# PJ30072S6_3V3_BOOST.net
KiCad netlist of a schematic drawn in Altium Designer
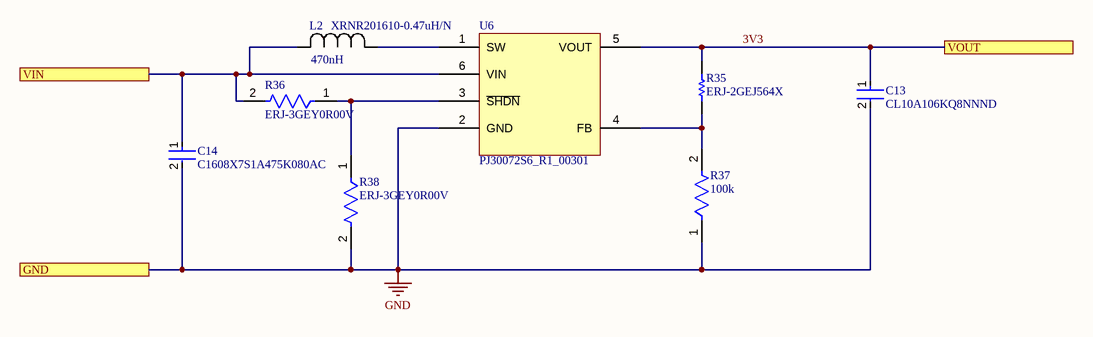
[diagram p0: PJ30072S6_3V3_BOOST.SchDoc]

(export (version "E")
  (design (tool "Eeschema 10.0.6"))
  (components
    (comp (ref "C13")
      (value "CL10A106KQ8NNND")
      (footprint "FP-CL10-IPC_C")
      (description "Cap Ceramic 10uF 6.3V X5R ±10% Pad SMD 0603 +85°C T/R")
      (fields (field (name "TOLERANCE") "10%"))
      (libsource (lib "Altium Content Vault") (part "b4654b650e69147ec39a6b967a45e02"))
    )
    (comp (ref "C14")
      (value "C1608X7S1A475K080AC")
      (footprint "FP-C1608-080-IPC_B")
      (description "CAP CER 4.7UF 10V X7S 0603")
      (fields (field (name "TOLERANCE") "10%"))
      (libsource (lib "Altium Content Vault") (part "b4654b650e69147ec39a6b967a45e02"))
    )
    (comp (ref "L2")
      (value "XRNR201610-0.47uH/N")
      (footprint "XRNR201610-0.47uH/N")
      (description "2.35A 2.3A 470nH 59mΩ Magnetic Shielded Inductor ±30% SMD-2P,2x1.6mm Power Inductors ROHS")
      (fields
        (field (name "MANUFACTURER") "Inpaq")
        (field (name "MANUFACTURER PART NUMBER") "WIP252012S-1R5MLDG")
        (field (name "INDUCTANCE") "470nH")
      )
      (libsource (lib "WIP252012S-R47MLDG") (part "XRNR201610-0.47uH/N"))
    )
    (comp (ref "R35")
      (value "ERJ-2GEJ564X")
      (footprint "RESC1005X40X25NL05T05")
      (fields (field (name "MANUFACTURER") "Panasonic"))
      (libsource (lib "Altium Content Vault") (part "RES"))
    )
    (comp (ref "R36")
      (value "ERJ-3GEY0R00V")
      (footprint "FP-ERJ-3GEY0R00V-MFG")
      (description "0 Ohms Jumper 0.1W, 1/10W Chip Resistor 0603 (1608 Metric) Automotive AEC-Q200 Thick Film")
      (fields (field (name "TOLERANCE") "5%"))
      (libsource (lib "Altium Content Vault") (part "1029c3af85768c4190bb7ad29bc67b5"))
    )
    (comp (ref "R37")
      (value "CRCW0402100KFKED")
      (footprint "FP-CRCW0402-e3-IPC_B")
      (description "RES Thick Film, 100kΩ, 1%, 0.063W, 100ppm/°C, 0402")
      (fields (field (name "RESISTANCE") "100k") (field (name "TOLERANCE") "1%"))
      (libsource (lib "Altium Content Vault") (part "1029c3af85768c4190bb7ad29bc67b5"))
    )
    (comp (ref "R38")
      (value "ERJ-3GEY0R00V")
      (footprint "FP-ERJ-3GEY0R00V-MFG")
      (description "0 Ohms Jumper 0.1W, 1/10W Chip Resistor 0603 (1608 Metric) Automotive AEC-Q200 Thick Film")
      (fields (field (name "TOLERANCE") "5%"))
      (libsource (lib "Altium Content Vault") (part "1029c3af85768c4190bb7ad29bc67b5"))
    )
    (comp (ref "U6")
      (value "PJ30072S6_R1_00301")
      (footprint "SOT95P280X15-6N")
      (description "IC REG BOOST ADJ SOT23-6")
      (libsource (lib "PJ30072S6_R1_00301") (part "PJ30072S6_R1_00301"))
    )
  )
  (nets
    (net (code "1") (name "/3V3") (class "Default")
      (node (ref "C13") (pin "1") (pinfunction "1_1") (pintype "passive"))
      (node (ref "R35") (pin "2") (pinfunction "2_2") (pintype "passive"))
      (node (ref "U6") (pin "5") (pinfunction "VOUT_5") (pintype "passive"))
    )
    (net (code "2") (name "/VIN") (class "Default")
      (node (ref "C14") (pin "1") (pinfunction "1_1") (pintype "passive"))
      (node (ref "L2") (pin "2") (pinfunction "2_2") (pintype "passive"))
      (node (ref "R36") (pin "2") (pinfunction "2_2") (pintype "passive"))
      (node (ref "U6") (pin "6") (pinfunction "VIN_6") (pintype "passive"))
    )
    (net (code "3") (name "GND") (class "Default")
      (node (ref "C13") (pin "2") (pinfunction "2_2") (pintype "passive"))
      (node (ref "C14") (pin "2") (pinfunction "2_2") (pintype "passive"))
      (node (ref "R37") (pin "1") (pinfunction "1_1") (pintype "passive"))
      (node (ref "R38") (pin "2") (pinfunction "2_2") (pintype "passive"))
      (node (ref "U6") (pin "2") (pinfunction "GND_2") (pintype "passive"))
    )
    (net (code "4") (name "Net-(U6-FB)") (class "Default")
      (node (ref "R35") (pin "1") (pinfunction "1_1") (pintype "passive"))
      (node (ref "R37") (pin "2") (pinfunction "2_2") (pintype "passive"))
      (node (ref "U6") (pin "4") (pinfunction "FB_4") (pintype "passive"))
    )
    (net (code "5") (name "Net-(U6-SW)") (class "Default")
      (node (ref "L2") (pin "1") (pinfunction "1_1") (pintype "passive"))
      (node (ref "U6") (pin "1") (pinfunction "SW_1") (pintype "passive"))
    )
    (net (code "6") (name "Net-(U6-~{SHDN})") (class "Default")
      (node (ref "R36") (pin "1") (pinfunction "1_1") (pintype "passive"))
      (node (ref "R38") (pin "1") (pinfunction "1_1") (pintype "passive"))
      (node (ref "U6") (pin "3") (pinfunction "~{SHDN}_3") (pintype "passive"))
    )
  )
)
